# eeprom.net
KiCad netlist of a schematic drawn in EAGLE
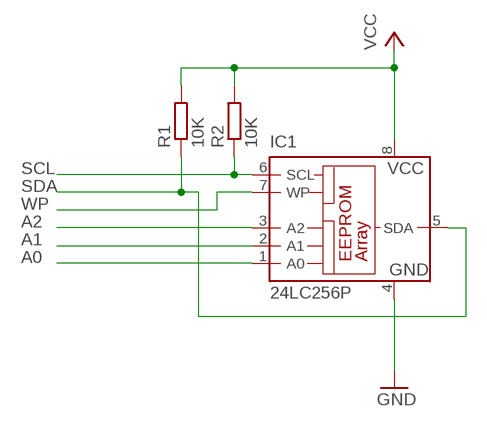
[diagram p0: schematic, sheet 1]

(export (version "E")
  (design (tool "Eeschema 10.0.6"))
  (components
    (comp (ref "IC1")
      (value "24LC256P")
      (footprint "eagle-import:DIL8")
      (fields (field (name "MF") "MICROCHIP") (field (name "MPN") "24LC256-E/P"))
      (libsource (lib "eagle-import") (part "24PLC256"))
    )
    (comp (ref "R1")
      (value "10K")
      (footprint "eagle-import:0204_7")
      (libsource (lib "eagle-import") (part "R-EU_0204/7"))
    )
    (comp (ref "R2")
      (value "10K")
      (footprint "eagle-import:0204_7")
      (libsource (lib "eagle-import") (part "R-EU_0204/7"))
    )
  )
  (nets
    (net (code "1") (name "/A0") (class "Default")
      (node (ref "IC1") (pin "1") (pinfunction "A0_1") (pintype "input"))
    )
    (net (code "2") (name "/A1") (class "Default")
      (node (ref "IC1") (pin "2") (pinfunction "A1_2") (pintype "input"))
    )
    (net (code "3") (name "/A2") (class "Default")
      (node (ref "IC1") (pin "3") (pinfunction "A2_3") (pintype "input"))
    )
    (net (code "4") (name "/SCL") (class "Default")
      (node (ref "IC1") (pin "6") (pinfunction "SCL_6") (pintype "input"))
      (node (ref "R2") (pin "1") (pinfunction "1_1") (pintype "passive"))
    )
    (net (code "5") (name "/SDA") (class "Default")
      (node (ref "IC1") (pin "5") (pinfunction "SDA_5") (pintype "bidirectional"))
      (node (ref "R1") (pin "1") (pinfunction "1_1") (pintype "passive"))
    )
    (net (code "6") (name "/WP") (class "Default")
      (node (ref "IC1") (pin "7") (pinfunction "WP_7") (pintype "input"))
    )
    (net (code "7") (name "GND") (class "Default")
      (node (ref "IC1") (pin "4") (pinfunction "GND_4") (pintype "power_in"))
    )
    (net (code "8") (name "VCC") (class "Default")
      (node (ref "IC1") (pin "8") (pinfunction "VCC_8") (pintype "power_in"))
      (node (ref "R1") (pin "2") (pinfunction "2_2") (pintype "passive"))
      (node (ref "R2") (pin "2") (pinfunction "2_2") (pintype "passive"))
    )
  )
)
